# buck_conv.net
KiCad netlist of a schematic drawn in Altium Designer
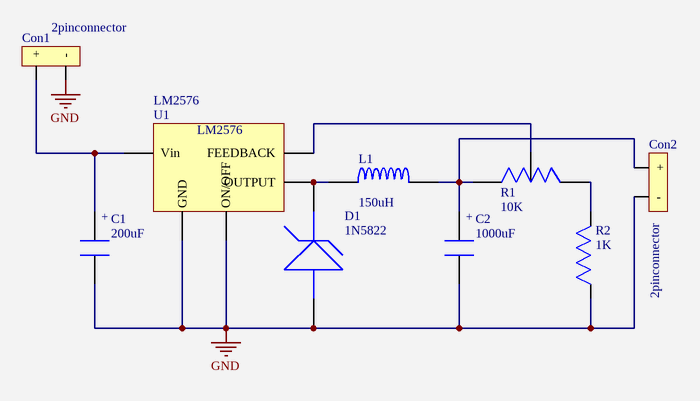
[diagram p0: buck_conv.SchDoc]

(export (version "E")
  (design (tool "Eeschema 10.0.6"))
  (components
    (comp (ref "C1")
      (value "200uF")
      (footprint "220uF Capacitor")
      (libsource (lib "LM2576_BuckConverter") (part "Electrolytic Cap 220uF"))
    )
    (comp (ref "C2")
      (value "1000uF")
      (footprint "1000Uf Cap")
      (libsource (lib "LM2576_BuckConverter") (part "Electrolytic Cap"))
    )
    (comp (ref "Con1")
      (value "2pinconnector")
      (footprint "2pin")
      (libsource (lib "") (part "2pinconnector_1"))
    )
    (comp (ref "Con2")
      (value "2pinconnector")
      (footprint "2pin")
      (libsource (lib "LM2576_BuckConverter") (part "2pinconnector"))
    )
    (comp (ref "D1")
      (value "1N5822")
      (footprint "1n5822")
      (libsource (lib "LM2576_BuckConverter") (part "1N5822"))
    )
    (comp (ref "L1")
      (value "150uH")
      (footprint "150uH Inductor")
      (libsource (lib "LM2576_BuckConverter") (part "150uH L"))
    )
    (comp (ref "R1")
      (value "10K")
      (footprint "10K Pot")
      (libsource (lib "LM2576_BuckConverter") (part "Variable Resistor"))
    )
    (comp (ref "R2")
      (value "1K")
      (footprint "1K 1206 Res")
      (libsource (lib "LM2576_BuckConverter") (part "Resistor"))
    )
    (comp (ref "U1")
      (value "LM2576")
      (footprint "LM2576-TO63-5")
      (libsource (lib "LM2576_BuckConverter") (part "LM2576"))
    )
  )
  (nets
    (net (code "1") (name "GND") (class "Default")
      (node (ref "C1") (pin "2") (pinfunction "2_2") (pintype "passive"))
      (node (ref "C2") (pin "2") (pinfunction "2_2") (pintype "passive"))
      (node (ref "Con1") (pin "2") (pinfunction "-_2") (pintype "passive"))
      (node (ref "Con2") (pin "2") (pinfunction "-_2") (pintype "passive"))
      (node (ref "D1") (pin "2") (pinfunction "2_2") (pintype "passive"))
      (node (ref "R2") (pin "1") (pinfunction "1_1") (pintype "passive"))
      (node (ref "U1") (pin "3") (pinfunction "GND_3") (pintype "passive"))
      (node (ref "U1") (pin "5") (pinfunction "ON/OFF_5") (pintype "passive"))
    )
    (net (code "2") (name "Net-(Con1-+)") (class "Default")
      (node (ref "C1") (pin "1") (pinfunction "1_1") (pintype "passive"))
      (node (ref "Con1") (pin "1") (pinfunction "+_1") (pintype "passive"))
      (node (ref "U1") (pin "1") (pinfunction "Vin_1") (pintype "passive"))
    )
    (net (code "3") (name "Net-(Con2-+)") (class "Default")
      (node (ref "C2") (pin "1") (pinfunction "1_1") (pintype "passive"))
      (node (ref "Con2") (pin "1") (pinfunction "+_1") (pintype "passive"))
      (node (ref "L1") (pin "2") (pinfunction "2_2") (pintype "passive"))
      (node (ref "R1") (pin "1") (pinfunction "1_1") (pintype "passive"))
    )
    (net (code "4") (name "Net-(R1-Pad3)") (class "Default")
      (node (ref "R1") (pin "3") (pinfunction "3_3") (pintype "passive"))
      (node (ref "R2") (pin "2") (pinfunction "2_2") (pintype "passive"))
    )
    (net (code "5") (name "Net-(U1-FEEDBACK)") (class "Default")
      (node (ref "R1") (pin "2") (pinfunction "2_2") (pintype "passive"))
      (node (ref "U1") (pin "4") (pinfunction "FEEDBACK_4") (pintype "passive"))
    )
    (net (code "6") (name "Net-(U1-OUTPUT)") (class "Default")
      (node (ref "D1") (pin "1") (pinfunction "1_1") (pintype "passive"))
      (node (ref "L1") (pin "1") (pinfunction "1_1") (pintype "passive"))
      (node (ref "U1") (pin "2") (pinfunction "OUTPUT_2") (pintype "passive"))
    )
  )
)
